# St1x.net
KiCad netlist of a schematic drawn in Altium Designer
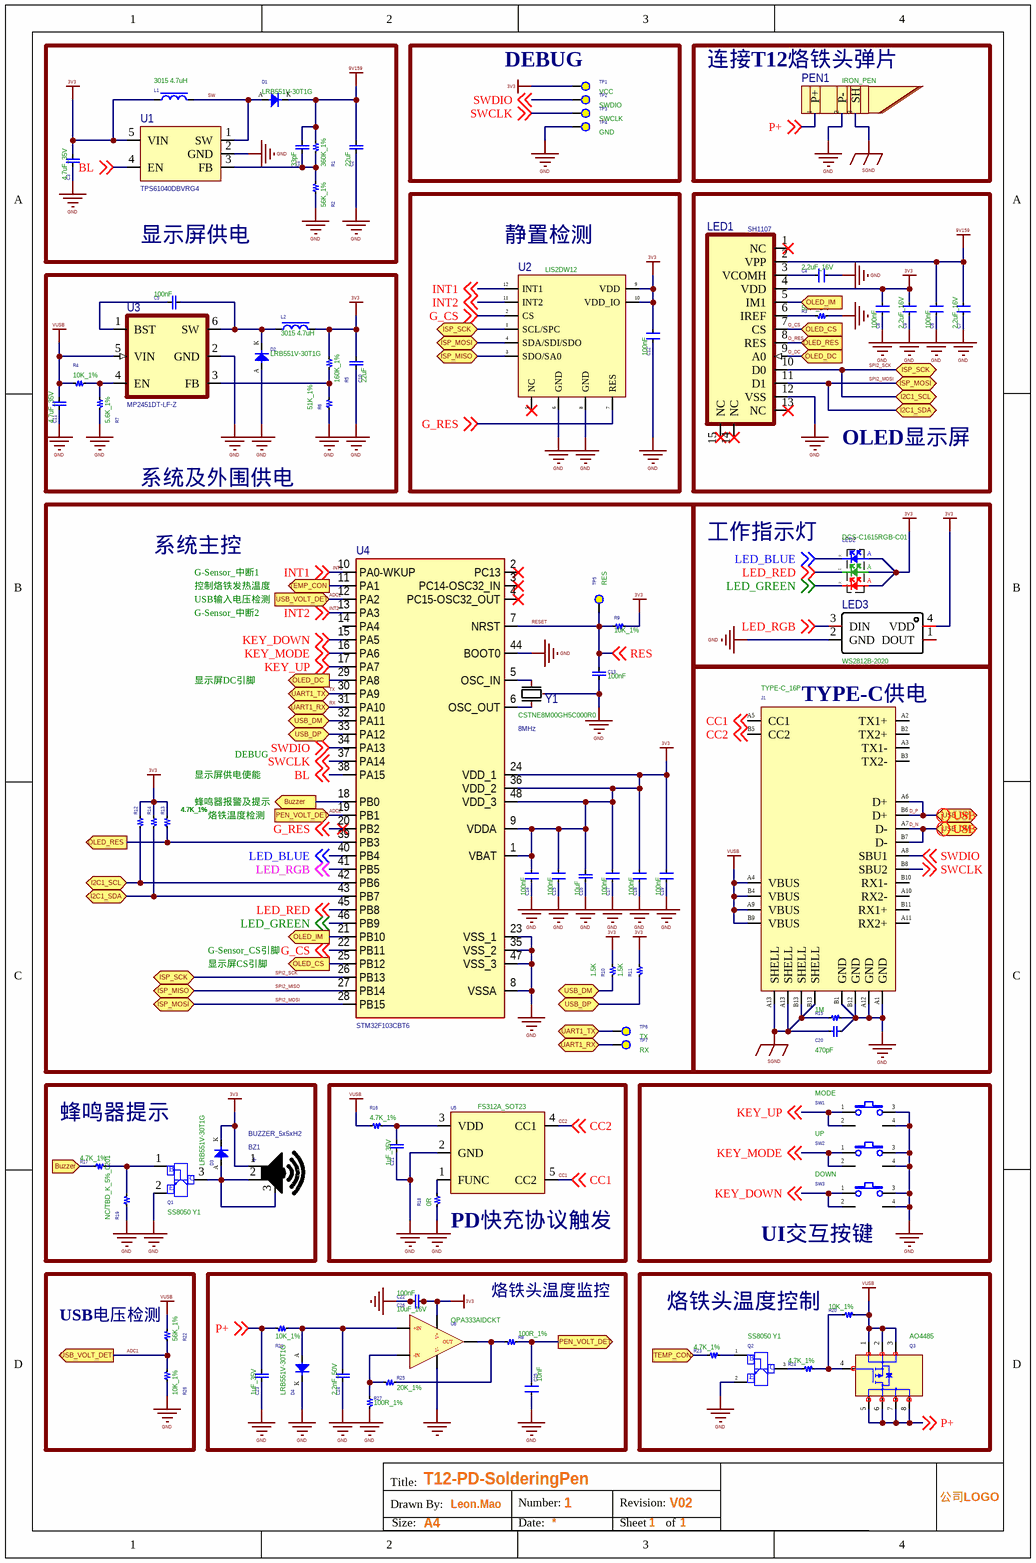
[diagram p0: St1x.SchDoc]

(export (version "E")
  (design (tool "Eeschema 10.0.6"))
  (components
    (comp (ref "BZ1")
      (value "BUZZER_5x5xH2")
      (footprint "BUZ-SMD_GSC5025YA")
      (description "电磁无源蜂鸣器(外部驱动)")
      (libsource (lib "SCHLIB_2022") (part "BZ"))
    )
    (comp (ref "C1")
      (value "33pF")
      (footprint "C1U0402")
      (description "贴片电容")
      (libsource (lib "SCHLIB_2022") (part "CAP_NP"))
    )
    (comp (ref "C2")
      (value "22uF")
      (footprint "CL0603")
      (description "贴片电容")
      (libsource (lib "SCHLIB_2022") (part "CAP_NP"))
    )
    (comp (ref "C3")
      (value "4.7uF_35V")
      (footprint "C4U0402")
      (description "贴片电容")
      (libsource (lib "SCHLIB_2022") (part "CAP_NP"))
    )
    (comp (ref "C4")
      (value "2.2uF_16V")
      (footprint "C4U0402")
      (description "贴片电容")
      (libsource (lib "") (part "CAP_NP_1"))
    )
    (comp (ref "C5")
      (value "100nF")
      (footprint "C1U0402")
      (description "贴片电容")
      (libsource (lib "SCHLIB_2022") (part "CAP_NP"))
    )
    (comp (ref "C6")
      (value "100nF")
      (footprint "C1U0402")
      (description "贴片电容")
      (libsource (lib "") (part "CAP_NP_1"))
    )
    (comp (ref "C7")
      (value "2.2uF_16V")
      (footprint "C4U0402")
      (description "贴片电容")
      (libsource (lib "") (part "CAP_NP_1"))
    )
    (comp (ref "C8")
      (value "100nF")
      (footprint "C1U0402")
      (description "贴片电容")
      (libsource (lib "") (part "CAP_NP_1"))
    )
    (comp (ref "C9")
      (value "2.2uF_16V")
      (footprint "C4U0402")
      (description "贴片电容")
      (libsource (lib "") (part "CAP_NP_1"))
    )
    (comp (ref "C10")
      (value "22uF")
      (footprint "CL0603")
      (description "贴片电容")
      (libsource (lib "SCHLIB_2022") (part "CAP_NP"))
    )
    (comp (ref "C11")
      (value "4.7uF_35V")
      (footprint "C4U0402")
      (description "贴片电容")
      (libsource (lib "SCHLIB_2022") (part "CAP_NP"))
    )
    (comp (ref "C12")
      (value "100nF")
      (footprint "C1U0402")
      (description "贴片电容")
      (libsource (lib "") (part "CAP_NP_1"))
    )
    (comp (ref "C13")
      (value "100nF")
      (footprint "C1U0402")
      (description "贴片电容")
      (libsource (lib "SCHLIB_2022") (part "CAP_NP"))
    )
    (comp (ref "C14")
      (value "100nF")
      (footprint "C1U0402")
      (description "贴片电容")
      (libsource (lib "") (part "CAP_NP_1"))
    )
    (comp (ref "C15")
      (value "100nF")
      (footprint "C1U0402")
      (description "贴片电容")
      (libsource (lib "") (part "CAP_NP_1"))
    )
    (comp (ref "C16")
      (value "10uF")
      (footprint "C4U0402")
      (description "贴片电容")
      (libsource (lib "SCHLIB_2022") (part "CAP_NP"))
    )
    (comp (ref "C17")
      (value "100nF")
      (footprint "C1U0402")
      (description "贴片电容")
      (libsource (lib "") (part "CAP_NP_1"))
    )
    (comp (ref "C18")
      (value "100nF")
      (footprint "C1U0402")
      (description "贴片电容")
      (libsource (lib "") (part "CAP_NP_1"))
    )
    (comp (ref "C19")
      (value "100nF")
      (footprint "C1U0402")
      (description "贴片电容")
      (libsource (lib "") (part "CAP_NP_1"))
    )
    (comp (ref "C20")
      (value "470pF")
      (footprint "C0402")
      (description "贴片电容")
      (libsource (lib "Leon") (part "CAP NP_1"))
    )
    (comp (ref "C21")
      (value "1uF_35V")
      (footprint "C1U0402")
      (description "贴片电容")
      (libsource (lib "SCHLIB_2022") (part "CAP_NP"))
    )
    (comp (ref "C22")
      (value "100nF")
      (footprint "C1U0402")
      (description "贴片电容")
      (libsource (lib "SCHLIB_2022") (part "CAP_NP"))
    )
    (comp (ref "C23")
      (value "1uF_35V")
      (footprint "C1U0402")
      (description "贴片电容")
      (libsource (lib "SCHLIB_2022") (part "CAP_NP"))
    )
    (comp (ref "C24")
      (value "2.2nF_50V")
      (footprint "C4U0402")
      (description "贴片电容")
      (libsource (lib "SCHLIB_2022") (part "CAP_NP"))
    )
    (comp (ref "C25")
      (value "10nF")
      (footprint "C1U0402")
      (description "贴片电容")
      (libsource (lib "") (part "CAP_NP_1"))
    )
    (comp (ref "C26")
      (value "10uF_16V")
      (footprint "C4U0402")
      (description "贴片电容")
      (libsource (lib "SCHLIB_2022") (part "CAP_NP"))
    )
    (comp (ref "D1")
      (value "LRB551V-30T1G")
      (footprint "SOD-323_AK")
      (description "肖特基二极管")
      (libsource (lib "Leon") (part "DIODE"))
    )
    (comp (ref "D2")
      (value "LRB551V-30T1G")
      (footprint "SOD-323_AK")
      (description "肖特基二极管")
      (libsource (lib "Leon") (part "DIODE"))
    )
    (comp (ref "D3")
      (value "LRB551V-30T1G")
      (footprint "SOD-323_AK")
      (description "肖特基二极管")
      (libsource (lib "Leon") (part "DIODE"))
    )
    (comp (ref "D4")
      (value "LRB551V-30T1G")
      (footprint "SOD-323_AK")
      (description "肖特基二极管")
      (libsource (lib "Leon") (part "DIODE"))
    )
    (comp (ref "J1")
      (value "TYPE-C_16P")
      (footprint "TYPE-C_16P")
      (description "TYPE-C母座")
      (libsource (lib "Leon") (part "TYPE-C_RI"))
    )
    (comp (ref "L1")
      (value "3015 4.7uH")
      (footprint "INDC3015")
      (description "功率电感")
      (libsource (lib "SCHLIB_2022") (part "INDUCTOR_2"))
    )
    (comp (ref "L2")
      (value "3015 4.7uH")
      (footprint "INDC3015")
      (description "功率电感")
      (libsource (lib "") (part "INDUCTOR_2_1"))
    )
    (comp (ref "LED1")
      (value "SH1107")
      (footprint "CON_13P_0.7mm-FPC")
      (description "QG-2880TSWKG01")
      (fields
        (field (name "MF") "{'manufacturer': u'Texas Instruments'}")
        (field (name "MP") "LP2985AIM5-5.0")
      )
      (libsource (lib "SCHLIB_2022") (part "SH1107"))
    )
    (comp (ref "LED2")
      (value "DCS-C1615RGB-C01")
      (footprint "RGB_DCS-C1615RGB-C01")
      (description "红绿蓝三色发光二极管")
      (libsource (lib "Leon") (part "LED_RGBS"))
    )
    (comp (ref "LED3")
      (value "WS2812B-2020")
      (footprint "LED_2020")
      (fields (field (name "MANUFACTURER PART") "Yo-WS2812B-3528反贴雾状"))
      (libsource (lib "altium-import") (part "root_0_mirrored_YO-WS2812B-3528反贴_"))
    )
    (comp (ref "PEN1") (value "IRON_PEN") (footprint "T13") (libsource (lib "SCHLIB_2022") (part "IRON_PEN")))
    (comp (ref "Q1")
      (value "SS8050 Y1")
      (footprint "SOT-23_123")
      (description "NPN三极管")
      (libsource (lib "PCBDEV_Library") (part "NPN"))
    )
    (comp (ref "Q2")
      (value "SS8050 Y1")
      (footprint "SOT-23_123")
      (description "NPN三极管")
      (libsource (lib "SCHLIB_2022") (part "NPN"))
    )
    (comp (ref "Q3")
      (value "AO4485")
      (footprint "SO-8M")
      (description "P沟道 40V 10A")
      (libsource (lib "SCHLIB_2022") (part "AO4485"))
    )
    (comp (ref "R1")
      (value "360K_1%")
      (footprint "RN0402")
      (description "贴片电阻")
      (libsource (lib "Leon") (part "ResSemi_3"))
    )
    (comp (ref "R2")
      (value "56K_1%")
      (footprint "RN0402")
      (description "贴片电阻")
      (libsource (lib "Leon") (part "ResSemi_3"))
    )
    (comp (ref "R3")
      (value "560k_1%")
      (footprint "RN0402")
      (description "贴片电阻")
      (libsource (lib "Leon") (part "ResSemi_3"))
    )
    (comp (ref "R4")
      (value "10K_1%")
      (footprint "RN0402")
      (description "贴片电阻")
      (libsource (lib "Leon") (part "ResSemi_3"))
    )
    (comp (ref "R5")
      (value "160K_1%")
      (footprint "RN0402")
      (description "贴片电阻")
      (libsource (lib "Leon") (part "ResSemi_3"))
    )
    (comp (ref "R6")
      (value "51K_1%")
      (footprint "RN0402")
      (description "贴片电阻")
      (libsource (lib "Leon") (part "ResSemi_3"))
    )
    (comp (ref "R7")
      (value "5.6K_1%")
      (footprint "RN0402")
      (description "贴片电阻")
      (libsource (lib "Leon") (part "ResSemi_3"))
    )
    (comp (ref "R8")
      (value "100R_1%")
      (footprint "RN0402")
      (description "贴片电阻")
      (libsource (lib "Leon") (part "ResSemi_3"))
    )
    (comp (ref "R9")
      (value "10K_1%")
      (footprint "RN0402")
      (description "贴片电阻")
      (libsource (lib "Leon") (part "ResSemi_3"))
    )
    (comp (ref "R10")
      (value "1.5K")
      (footprint "RN0402")
      (description "贴片电阻")
      (libsource (lib "Leon") (part "ResSemi_3"))
    )
    (comp (ref "R11")
      (value "1.5K")
      (footprint "RN0402")
      (description "贴片电阻")
      (libsource (lib "Leon") (part "ResSemi_3"))
    )
    (comp (ref "R12")
      (value "4.7K_1%")
      (footprint "RN0402")
      (description "贴片电阻")
      (libsource (lib "Leon") (part "ResSemi_3"))
    )
    (comp (ref "R13")
      (value "4.7K_1%")
      (footprint "RN0402")
      (description "贴片电阻")
      (libsource (lib "Leon") (part "ResSemi_3"))
    )
    (comp (ref "R14")
      (value "4.7K_1%")
      (footprint "RN0402")
      (description "贴片电阻")
      (libsource (lib "Leon") (part "ResSemi_3"))
    )
    (comp (ref "R15")
      (value "1M")
      (footprint "RN0402")
      (description "贴片电阻")
      (libsource (lib "Leon") (part "ResSemi_3"))
    )
    (comp (ref "R16")
      (value "4.7K_1%")
      (footprint "RN0402")
      (description "贴片电阻")
      (libsource (lib "Leon") (part "ResSemi_3"))
    )
    (comp (ref "R17")
      (value "4.7K_1%")
      (footprint "RN0402")
      (description "贴片电阻")
      (libsource (lib "Leon") (part "ResSemi_3"))
    )
    (comp (ref "R18")
      (value "0R")
      (footprint "RN0402")
      (description "贴片电阻")
      (libsource (lib "Leon") (part "ResSemi_3"))
    )
    (comp (ref "R19")
      (value "NC/TBD_K_5%_0201")
      (footprint "RN0402")
      (description "贴片电阻")
      (libsource (lib "Leon") (part "ResSemi_3"))
    )
    (comp (ref "R20")
      (value "10K_1%")
      (footprint "RN0402")
      (description "贴片电阻")
      (libsource (lib "Leon") (part "ResSemi_3"))
    )
    (comp (ref "R21")
      (value "10K_1%")
      (footprint "RN0603")
      (description "贴片电阻")
      (libsource (lib "Leon") (part "ResSemi_3"))
    )
    (comp (ref "R22")
      (value "56K_1%")
      (footprint "RN0402")
      (description "贴片电阻")
      (libsource (lib "Leon") (part "ResSemi_3"))
    )
    (comp (ref "R23")
      (value "4.7K_1%")
      (footprint "RN0402")
      (description "贴片电阻")
      (libsource (lib "Leon") (part "ResSemi_3"))
    )
    (comp (ref "R24")
      (value "4.7K_1%")
      (footprint "RN0402")
      (description "贴片电阻")
      (libsource (lib "Leon") (part "ResSemi_3"))
    )
    (comp (ref "R25")
      (value "20K_1%")
      (footprint "RN0402")
      (description "贴片电阻")
      (libsource (lib "Leon") (part "ResSemi_3"))
    )
    (comp (ref "R26")
      (value "10K_1%")
      (footprint "RN0402")
      (description "贴片电阻")
      (libsource (lib "Leon") (part "ResSemi_3"))
    )
    (comp (ref "R27")
      (value "100R_1%")
      (footprint "RN0402")
      (description "贴片电阻")
      (libsource (lib "Leon") (part "ResSemi_3"))
    )
    (comp (ref "SW1")
      (value "MODE")
      (footprint "KEY-SMD_4P-L4.2-W3.2-P2.20-LS5.1-TL")
      (description "轻触开关")
      (libsource (lib "SCHLIB_2022") (part "SW PUSHBUTTON"))
    )
    (comp (ref "SW2")
      (value "UP")
      (footprint "KEY-SMD_4P-L4.2-W3.2-P2.20-LS5.1-TL")
      (description "轻触开关")
      (libsource (lib "SCHLIB_2022") (part "SW PUSHBUTTON"))
    )
    (comp (ref "SW3")
      (value "DOWN")
      (footprint "KEY-SMD_4P-L4.2-W3.2-P2.20-LS5.1-TL")
      (description "轻触开关")
      (libsource (lib "SCHLIB_2022") (part "SW PUSHBUTTON"))
    )
    (comp (ref "TP1") (value "VCC") (footprint "SMD0808") (libsource (lib "SCHLIB_2022") (part "TEST")))
    (comp (ref "TP2") (value "SWDIO") (footprint "SMD0808") (libsource (lib "SCHLIB_2022") (part "TEST")))
    (comp (ref "TP3") (value "SWCLK") (footprint "SMD0808") (libsource (lib "SCHLIB_2022") (part "TEST")))
    (comp (ref "TP4") (value "GND") (footprint "SMD0808") (libsource (lib "SCHLIB_2022") (part "TEST")))
    (comp (ref "TP5") (value "RES") (footprint "SMD0808") (libsource (lib "SCHLIB_2022") (part "TEST")))
    (comp (ref "TP6") (value "TX") (footprint "SMD0808") (libsource (lib "SCHLIB_2022") (part "TEST")))
    (comp (ref "TP7") (value "RX") (footprint "SMD0808") (libsource (lib "SCHLIB_2022") (part "TEST")))
    (comp (ref "U1")
      (value "TPS61040DBVRG4")
      (footprint "SOT23-5")
      (description "DC-DC芯片")
      (libsource (lib "SCHLIB_2022") (part "TPS61040DBVRG4_[C7722]"))
    )
    (comp (ref "U2")
      (value "LIS2DW12")
      (footprint "LGA12_20x20x07")
      (libsource (lib "SCHLIB_2022") (part "LIS2DW12"))
    )
    (comp (ref "U3")
      (value "MP2451DT-LF-Z")
      (footprint "SOT23-6")
      (fields
        (field (name "MF") "{'manufacturer': u'Texas Instruments'}")
        (field (name "MP") "LP2985AIM5-5.0")
      )
      (libsource (lib "SCHLIB_2022") (part "MP2451DT-LF-Z"))
    )
    (comp (ref "U4")
      (value "STM32F103CBT6")
      (footprint "LQFP48-7x7mm")
      (description "No Description Available")
      (fields (field (name "COPYRIGHT") "Copyright (C) 2023 Ultra Librarian. All rights reserved."))
      (libsource (lib "SCHLIB_2022") (part "STM32F103CBT6"))
    )
    (comp (ref "U5")
      (value "FS312A_SOT23")
      (footprint "SOT23-5")
      (description "USB Type-C PD快充协议智能触发芯片")
      (libsource (lib "SCHLIB_2022") (part "FS312A"))
    )
    (comp (ref "U6")
      (value "OPA333AIDCKT")
      (footprint "SOT23-5")
      (libsource (lib "SCHLIB_2022") (part "OPA333_SOT23"))
    )
    (comp (ref "Y1")
      (value "CSTNE8M00GH5C000R0")
      (footprint "OSC-SMD_3P-L3.2-W1.3-P1.20-L")
      (description "频率:8MHz;频率容差:±0.07%;内藏负载电容:33pF;谐振阻抗:40Ω;")
      (fields (field (name "MANUFACTURER") "muRata(村田)") (field (name "ALTIUM_VALUE") "8MHz"))
      (libsource (lib "SCHLIB_2022") (part "CSTNE8M00GH5C000R0"))
    )
  )
  (nets
    (net (code "1") (name "/ADC1") (class "Default")
      (node (ref "R22") (pin "1") (pinfunction "1_1") (pintype "passive"))
      (node (ref "R26") (pin "2") (pinfunction "2_2") (pintype "passive"))
      (node (ref "U4") (pin "12") (pinfunction "PA2_12") (pintype "passive"))
    )
    (net (code "2") (name "/ADC2") (class "Default")
      (node (ref "C25") (pin "1") (pinfunction "1_1") (pintype "passive"))
      (node (ref "R8") (pin "1") (pinfunction "1_1") (pintype "passive"))
      (node (ref "U4") (pin "19") (pinfunction "PB1_19") (pintype "passive"))
    )
    (net (code "3") (name "/Buzzer") (class "Default")
      (node (ref "R17") (pin "1") (pinfunction "1_1") (pintype "passive"))
      (node (ref "U4") (pin "18") (pinfunction "PB0_18") (pintype "passive"))
    )
    (net (code "4") (name "/D_N") (class "Default")
      (node (ref "J1") (pin "A7") (pinfunction "D-_A7") (pintype "passive"))
      (node (ref "J1") (pin "B7") (pinfunction "D-_B7") (pintype "passive"))
      (node (ref "R10") (pin "2") (pinfunction "2_2") (pintype "passive"))
      (node (ref "U4") (pin "32") (pinfunction "PA11_32") (pintype "passive"))
    )
    (net (code "5") (name "/D_P") (class "Default")
      (node (ref "J1") (pin "A6") (pinfunction "D+_A6") (pintype "passive"))
      (node (ref "J1") (pin "B6") (pinfunction "D+_B6") (pintype "passive"))
      (node (ref "R11") (pin "2") (pinfunction "2_2") (pintype "passive"))
      (node (ref "U4") (pin "33") (pinfunction "PA12_33") (pintype "passive"))
    )
    (net (code "6") (name "/OLED_IM") (class "Default")
      (node (ref "LED1") (pin "5") (pinfunction "IM1_5") (pintype "passive"))
      (node (ref "U4") (pin "21") (pinfunction "PB10_21") (pintype "passive"))
    )
    (net (code "7") (name "/O_CS") (class "Default")
      (node (ref "LED1") (pin "7") (pinfunction "CS_7") (pintype "passive"))
      (node (ref "U4") (pin "25") (pinfunction "PB12_25") (pintype "passive"))
    )
    (net (code "8") (name "/O_DC") (class "Default")
      (node (ref "LED1") (pin "9") (pinfunction "A0_9") (pintype "input"))
      (node (ref "U4") (pin "29") (pinfunction "PA8_29") (pintype "passive"))
    )
    (net (code "9") (name "/O_RES") (class "Default")
      (node (ref "LED1") (pin "8") (pinfunction "RES_8") (pintype "passive"))
      (node (ref "R13") (pin "2") (pinfunction "2_2") (pintype "passive"))
      (node (ref "U4") (pin "39") (pinfunction "PB3_39") (pintype "passive"))
    )
    (net (code "10") (name "/RX") (class "Default")
      (node (ref "TP7") (pin "1") (pinfunction "1_1") (pintype "passive"))
      (node (ref "U4") (pin "31") (pinfunction "PA10_31") (pintype "passive"))
    )
    (net (code "11") (name "/SPI2_MISO") (class "Default")
      (node (ref "U2") (pin "3") (pinfunction "SDO/SA0_3") (pintype "passive"))
      (node (ref "U4") (pin "27") (pinfunction "PB14_27") (pintype "passive"))
    )
    (net (code "12") (name "/SPI2_MOSI") (class "Default")
      (node (ref "LED1") (pin "11") (pinfunction "D1_11") (pintype "passive"))
      (node (ref "R14") (pin "1") (pinfunction "1_1") (pintype "passive"))
      (node (ref "U2") (pin "4") (pinfunction "SDA/SDI/SDO_4") (pintype "passive"))
      (node (ref "U4") (pin "28") (pinfunction "PB15_28") (pintype "passive"))
      (node (ref "U4") (pin "43") (pinfunction "PB7_43") (pintype "passive"))
    )
    (net (code "13") (name "/SPI2_SCK") (class "Default")
      (node (ref "LED1") (pin "10") (pinfunction "D0_10") (pintype "passive"))
      (node (ref "R12") (pin "1") (pinfunction "1_1") (pintype "passive"))
      (node (ref "U2") (pin "1") (pinfunction "SCL/SPC_1") (pintype "passive"))
      (node (ref "U4") (pin "26") (pinfunction "PB13_26") (pintype "passive"))
      (node (ref "U4") (pin "42") (pinfunction "PB6_42") (pintype "passive"))
    )
    (net (code "14") (name "/SW") (class "Default")
      (node (ref "D1") (pin "A") (pinfunction "ANODE_A") (pintype "passive"))
      (node (ref "L1") (pin "2") (pinfunction "2_2") (pintype "passive"))
      (node (ref "U1") (pin "1") (pinfunction "SW_1") (pintype "passive"))
    )
    (net (code "15") (name "/TEMP_CON") (class "Default")
      (node (ref "R23") (pin "1") (pinfunction "1_1") (pintype "passive"))
      (node (ref "U4") (pin "11") (pinfunction "PA1_11") (pintype "passive"))
    )
    (net (code "16") (name "/TX") (class "Default")
      (node (ref "TP6") (pin "1") (pinfunction "1_1") (pintype "passive"))
      (node (ref "U4") (pin "30") (pinfunction "PA9_30") (pintype "passive"))
    )
    (net (code "17") (name "3V3") (class "Default")
      (node (ref "BZ1") (pin "1") (pinfunction "+_1") (pintype "passive"))
      (node (ref "C10") (pin "2") (pinfunction "2_2") (pintype "passive"))
      (node (ref "C12") (pin "1") (pinfunction "1_1") (pintype "passive"))
      (node (ref "C14") (pin "1") (pinfunction "1_1") (pintype "passive"))
      (node (ref "C15") (pin "1") (pinfunction "1_1") (pintype "passive"))
      (node (ref "C16") (pin "2") (pinfunction "2_2") (pintype "passive"))
      (node (ref "C17") (pin "1") (pinfunction "1_1") (pintype "passive"))
      (node (ref "C18") (pin "1") (pinfunction "1_1") (pintype "passive"))
      (node (ref "C19") (pin "1") (pinfunction "1_1") (pintype "passive"))
      (node (ref "C22") (pin "2") (pinfunction "2_2") (pintype "passive"))
      (node (ref "C26") (pin "1") (pinfunction "1_1") (pintype "passive"))
      (node (ref "C3") (pin "2") (pinfunction "2_2") (pintype "passive"))
      (node (ref "C8") (pin "1") (pinfunction "1_1") (pintype "passive"))
      (node (ref "C9") (pin "1") (pinfunction "1_1") (pintype "passive"))
      (node (ref "D3") (pin "K") (pinfunction "CATHODE_K") (pintype "passive"))
      (node (ref "L1") (pin "1") (pinfunction "1_1") (pintype "passive"))
      (node (ref "L2") (pin "1") (pinfunction "1_1") (pintype "passive"))
      (node (ref "LED1") (pin "4") (pinfunction "VDD_4") (pintype "power_in"))
      (node (ref "LED2") (pin "A") (pinfunction "A_A") (pintype "passive"))
      (node (ref "LED3") (pin "4") (pinfunction "VDD_4") (pintype "passive"))
      (node (ref "R10") (pin "1") (pinfunction "1_1") (pintype "passive"))
      (node (ref "R11") (pin "1") (pinfunction "1_1") (pintype "passive"))
      (node (ref "R12") (pin "2") (pinfunction "2_2") (pintype "passive"))
      (node (ref "R13") (pin "1") (pinfunction "1_1") (pintype "passive"))
      (node (ref "R14") (pin "2") (pinfunction "2_2") (pintype "passive"))
      (node (ref "R5") (pin "1") (pinfunction "1_1") (pintype "passive"))
      (node (ref "R9") (pin "1") (pinfunction "1_1") (pintype "passive"))
      (node (ref "TP1") (pin "1") (pinfunction "1_1") (pintype "passive"))
      (node (ref "U1") (pin "5") (pinfunction "VIN_5") (pintype "passive"))
      (node (ref "U2") (pin "10") (pinfunction "VDD_IO_10") (pintype "passive"))
      (node (ref "U2") (pin "9") (pinfunction "VDD_9") (pintype "passive"))
      (node (ref "U4") (pin "1") (pinfunction "VBAT_1") (pintype "power_in"))
      (node (ref "U4") (pin "24") (pinfunction "VDD_1_24") (pintype "power_in"))
      (node (ref "U4") (pin "36") (pinfunction "VDD_2_36") (pintype "power_in"))
      (node (ref "U4") (pin "48") (pinfunction "VDD_3_48") (pintype "power_in"))
      (node (ref "U4") (pin "9") (pinfunction "VDDA_9") (pintype "power_in"))
      (node (ref "U6") (pin "5") (pinfunction "V+_5") (pintype "passive"))
    )
    (net (code "18") (name "9V159") (class "Default")
      (node (ref "C1") (pin "2") (pinfunction "2_2") (pintype "passive"))
      (node (ref "C2") (pin "2") (pinfunction "2_2") (pintype "passive"))
      (node (ref "C6") (pin "1") (pinfunction "1_1") (pintype "passive"))
      (node (ref "C7") (pin "1") (pinfunction "1_1") (pintype "passive"))
      (node (ref "D1") (pin "K") (pinfunction "CATHODE_K") (pintype "passive"))
      (node (ref "LED1") (pin "2") (pinfunction "VPP_2") (pintype "power_in"))
      (node (ref "R1") (pin "1") (pinfunction "1_1") (pintype "passive"))
    )
    (net (code "19") (name "BL") (class "Default")
      (node (ref "U1") (pin "4") (pinfunction "EN_4") (pintype "passive"))
      (node (ref "U4") (pin "38") (pinfunction "PA15_38") (pintype "passive"))
    )
    (net (code "20") (name "CC1") (class "Default")
      (node (ref "J1") (pin "A5") (pinfunction "CC1_A5") (pintype "passive"))
      (node (ref "U5") (pin "5") (pinfunction "CC2_5") (pintype "passive"))
    )
    (net (code "21") (name "CC2") (class "Default")
      (node (ref "J1") (pin "B5") (pinfunction "CC2_B5") (pintype "passive"))
      (node (ref "U5") (pin "4") (pinfunction "CC1_4") (pintype "passive"))
    )
    (net (code "22") (name "GND") (class "Default")
      (node (ref "C10") (pin "1") (pinfunction "1_1") (pintype "passive"))
      (node (ref "C11") (pin "1") (pinfunction "1_1") (pintype "passive"))
      (node (ref "C12") (pin "2") (pinfunction "2_2") (pintype "passive"))
      (node (ref "C13") (pin "2") (pinfunction "2_2") (pintype "passive"))
      (node (ref "C14") (pin "2") (pinfunction "2_2") (pintype "passive"))
      (node (ref "C15") (pin "2") (pinfunction "2_2") (pintype "passive"))
      (node (ref "C16") (pin "1") (pinfunction "1_1") (pintype "passive"))
      (node (ref "C17") (pin "2") (pinfunction "2_2") (pintype "passive"))
      (node (ref "C18") (pin "2") (pinfunction "2_2") (pintype "passive"))
      (node (ref "C19") (pin "2") (pinfunction "2_2") (pintype "passive"))
      (node (ref "C2") (pin "1") (pinfunction "1_1") (pintype "passive"))
      (node (ref "C20") (pin "1") (pinfunction "1_1") (pintype "passive"))
      (node (ref "C21") (pin "1") (pinfunction "1_1") (pintype "passive"))
      (node (ref "C22") (pin "1") (pinfunction "1_1") (pintype "passive"))
      (node (ref "C23") (pin "2") (pinfunction "2_2") (pintype "passive"))
      (node (ref "C24") (pin "2") (pinfunction "2_2") (pintype "passive"))
      (node (ref "C25") (pin "2") (pinfunction "2_2") (pintype "passive"))
      (node (ref "C26") (pin "2") (pinfunction "2_2") (pintype "passive"))
      (node (ref "C3") (pin "1") (pinfunction "1_1") (pintype "passive"))
      (node (ref "C4") (pin "2") (pinfunction "2_2") (pintype "passive"))
      (node (ref "C6") (pin "2") (pinfunction "2_2") (pintype "passive"))
      (node (ref "C7") (pin "2") (pinfunction "2_2") (pintype "passive"))
      (node (ref "C8") (pin "2") (pinfunction "2_2") (pintype "passive"))
      (node (ref "C9") (pin "2") (pinfunction "2_2") (pintype "passive"))
      (node (ref "D2") (pin "A") (pinfunction "ANODE_A") (pintype "passive"))
      (node (ref "D4") (pin "K") (pinfunction "CATHODE_K") (pintype "passive"))
      (node (ref "J1") (pin "A1") (pinfunction "GND_A1") (pintype "passive"))
      (node (ref "J1") (pin "A12") (pinfunction "GND_A12") (pintype "passive"))
      (node (ref "J1") (pin "B1") (pinfunction "GND_B1") (pintype "passive"))
      (node (ref "J1") (pin "B12") (pinfunction "GND_B12") (pintype "passive"))
      (node (ref "LED1") (pin "12") (pinfunction "VSS_12") (pintype "passive"))
      (node (ref "LED3") (pin "2") (pinfunction "GND_2") (pintype "passive"))
      (node (ref "PEN1") (pin "2") (pinfunction "P-_2") (pintype "passive"))
      (node (ref "Q1") (pin "2") (pinfunction "EMITTER_2") (pintype "passive"))
      (node (ref "Q2") (pin "2") (pinfunction "EMITTER_2") (pintype "passive"))
      (node (ref "R15") (pin "2") (pinfunction "2_2") (pintype "passive"))
      (node (ref "R18") (pin "2") (pinfunction "2_2") (pintype "passive"))
      (node (ref "R19") (pin "1") (pinfunction "1_1") (pintype "passive"))
      (node (ref "R2") (pin "1") (pinfunction "1_1") (pintype "passive"))
      (node (ref "R26") (pin "1") (pinfunction "1_1") (pintype "passive"))
      (node (ref "R27") (pin "2") (pinfunction "2_2") (pintype "passive"))
      (node (ref "R3") (pin "1") (pinfunction "1_1") (pintype "passive"))
      (node (ref "R6") (pin "1") (pinfunction "1_1") (pintype "passive"))
      (node (ref "R7") (pin "2") (pinfunction "2_2") (pintype "passive"))
      (node (ref "SW1") (pin "3") (pinfunction "3_3") (pintype "passive"))
      (node (ref "SW1") (pin "4") (pinfunction "4_4") (pintype "passive"))
      (node (ref "SW2") (pin "3") (pinfunction "3_3") (pintype "passive"))
      (node (ref "SW2") (pin "4") (pinfunction "4_4") (pintype "passive"))
      (node (ref "SW3") (pin "3") (pinfunction "3_3") (pintype "passive"))
      (node (ref "SW3") (pin "4") (pinfunction "4_4") (pintype "passive"))
      (node (ref "TP4") (pin "1") (pinfunction "1_1") (pintype "passive"))
      (node (ref "U1") (pin "2") (pinfunction "GND_2") (pintype "passive"))
      (node (ref "U2") (pin "6") (pinfunction "GND_6") (pintype "passive"))
      (node (ref "U2") (pin "8") (pinfunction "GND_8") (pintype "passive"))
      (node (ref "U3") (pin "2") (pinfunction "GND_2") (pintype "power_in"))
      (node (ref "U4") (pin "23") (pinfunction "VSS_1_23") (pintype "power_in"))
      (node (ref "U4") (pin "35") (pinfunction "VSS_2_35") (pintype "power_in"))
      (node (ref "U4") (pin "44") (pinfunction "BOOT0_44") (pintype "passive"))
      (node (ref "U4") (pin "47") (pinfunction "VSS_3_47") (pintype "power_in"))
      (node (ref "U4") (pin "8") (pinfunction "VSSA_8") (pintype "power_in"))
      (node (ref "U5") (pin "2") (pinfunction "GND_2") (pintype "passive"))
      (node (ref "U6") (pin "2") (pinfunction "V-_2") (pintype "passive"))
      (node (ref "Y1") (pin "2") (pinfunction "GND_2") (pintype "passive"))
    )
    (net (code "23") (name "G_CS") (class "Default")
      (node (ref "U2") (pin "2") (pinfunction "CS_2") (pintype "passive"))
      (node (ref "U4") (pin "22") (pinfunction "PB11_22") (pintype "passive"))
    )
    (net (code "24") (name "G_RES") (class "Default")
      (node (ref "U2") (pin "7") (pinfunction "RES_7") (pintype "passive"))
      (node (ref "U4") (pin "20") (pinfunction "PB2_20") (pintype "passive"))
    )
    (net (code "25") (name "INT1") (class "Default")
      (node (ref "U2") (pin "12") (pinfunction "INT1_12") (pintype "passive"))
      (node (ref "U4") (pin "10") (pinfunction "PA0-WKUP_10") (pintype "passive"))
    )
    (net (code "26") (name "INT2") (class "Default")
      (node (ref "U2") (pin "11") (pinfunction "INT2_11") (pintype "passive"))
      (node (ref "U4") (pin "13") (pinfunction "PA3_13") (pintype "passive"))
    )
    (net (code "27") (name "KEY_DOWN") (class "Default")
      (node (ref "SW3") (pin "1") (pinfunction "1_1") (pintype "passive"))
      (node (ref "SW3") (pin "2") (pinfunction "2_2") (pintype "passive"))
      (node (ref "U4") (pin "15") (pinfunction "PA5_15") (pintype "passive"))
    )
    (net (code "28") (name "KEY_MODE") (class "Default")
      (node (ref "SW2") (pin "1") (pinfunction "1_1") (pintype "passive"))
      (node (ref "SW2") (pin "2") (pinfunction "2_2") (pintype "passive"))
      (node (ref "U4") (pin "16") (pinfunction "PA6_16") (pintype "passive"))
    )
    (net (code "29") (name "KEY_UP") (class "Default")
      (node (ref "SW1") (pin "1") (pinfunction "1_1") (pintype "passive"))
      (node (ref "SW1") (pin "2") (pinfunction "2_2") (pintype "passive"))
      (node (ref "U4") (pin "17") (pinfunction "PA7_17") (pintype "passive"))
    )
    (net (code "30") (name "LED_BLUE") (class "Default")
      (node (ref "LED2") (pin "BC") (pinfunction "BC_BC") (pintype "passive"))
      (node (ref "U4") (pin "40") (pinfunction "PB4_40") (pintype "passive"))
    )
    (net (code "31") (name "LED_GREEN") (class "Default")
      (node (ref "LED2") (pin "RC") (pinfunction "RC_RC") (pintype "passive"))
      (node (ref "U4") (pin "46") (pinfunction "PB9_46") (pintype "passive"))
    )
    (net (code "32") (name "LED_RED") (class "Default")
      (node (ref "LED2") (pin "GC") (pinfunction "GC_GC") (pintype "passive"))
      (node (ref "U4") (pin "45") (pinfunction "PB8_45") (pintype "passive"))
    )
    (net (code "33") (name "LED_RGB") (class "Default")
      (node (ref "LED3") (pin "3") (pinfunction "DIN_3") (pintype "passive"))
      (node (ref "U4") (pin "41") (pinfunction "PB5_41") (pintype "passive"))
    )
    (net (code "34") (name "Net-(D2-CATHODE)") (class "Default")
      (node (ref "C5") (pin "1") (pinfunction "1_1") (pintype "passive"))
      (node (ref "D2") (pin "K") (pinfunction "CATHODE_K") (pintype "passive"))
      (node (ref "L2") (pin "2") (pinfunction "2_2") (pintype "passive"))
      (node (ref "U3") (pin "6") (pinfunction "SW_6") (pintype "passive"))
    )
    (net (code "35") (name "Net-(D3-ANODE)") (class "Default")
      (node (ref "BZ1") (pin "2") (pinfunction "-_2") (pintype "passive"))
      (node (ref "BZ1") (pin "3") (pinfunction "-_3") (pintype "passive"))
      (node (ref "D3") (pin "A") (pinfunction "ANODE_A") (pintype "passive"))
      (node (ref "Q1") (pin "3") (pinfunction "COLLECTOR_3") (pintype "passive"))
    )
    (net (code "36") (name "Net-(D4-ANODE)") (class "Default")
      (node (ref "C24") (pin "1") (pinfunction "1_1") (pintype "passive"))
      (node (ref "D4") (pin "A") (pinfunction "ANODE_A") (pintype "passive"))
      (node (ref "R21") (pin "1") (pinfunction "1_1") (pintype "passive"))
      (node (ref "U6") (pin "3") (pinfunction "+IN_3") (pintype "passive"))
    )
    (net (code "37") (name "Net-(LED1-IREF)") (class "Default")
      (node (ref "LED1") (pin "6") (pinfunction "IREF_6") (pintype "passive"))
      (node (ref "R3") (pin "2") (pinfunction "2_2") (pintype "passive"))
    )
    (net (code "38") (name "Net-(LED1-VCOMH)") (class "Default")
      (node (ref "C4") (pin "1") (pinfunction "1_1") (pintype "passive"))
      (node (ref "LED1") (pin "3") (pinfunction "VCOMH_3") (pintype "passive"))
    )
    (net (code "39") (name "Net-(Q1-BASE)") (class "Default")
      (node (ref "Q1") (pin "1") (pinfunction "BASE_1") (pintype "passive"))
      (node (ref "R17") (pin "2") (pinfunction "2_2") (pintype "passive"))
      (node (ref "R19") (pin "2") (pinfunction "2_2") (pintype "passive"))
    )
    (net (code "40") (name "Net-(Q2-BASE)") (class "Default")
      (node (ref "Q2") (pin "1") (pinfunction "BASE_1") (pintype "passive"))
      (node (ref "R23") (pin "2") (pinfunction "2_2") (pintype "passive"))
    )
    (net (code "41") (name "Net-(Q2-COLLECTOR)") (class "Default")
      (node (ref "Q2") (pin "3") (pinfunction "COLLECTOR_3") (pintype "passive"))
      (node (ref "R24") (pin "1") (pinfunction "1_1") (pintype "passive"))
    )
    (net (code "42") (name "Net-(Q3-G)") (class "Default")
      (node (ref "Q3") (pin "4") (pinfunction "G_4") (pintype "passive"))
      (node (ref "R20") (pin "1") (pinfunction "1_1") (pintype "passive"))
      (node (ref "R24") (pin "2") (pinfunction "2_2") (pintype "passive"))
    )
    (net (code "43") (name "Net-(U1-FB)") (class "Default")
      (node (ref "C1") (pin "1") (pinfunction "1_1") (pintype "passive"))
      (node (ref "R1") (pin "2") (pinfunction "2_2") (pintype "passive"))
      (node (ref "R2") (pin "2") (pinfunction "2_2") (pintype "passive"))
      (node (ref "U1") (pin "3") (pinfunction "FB_3") (pintype "passive"))
    )
    (net (code "44") (name "Net-(U3-BST)") (class "Default")
      (node (ref "C5") (pin "2") (pinfunction "2_2") (pintype "passive"))
      (node (ref "U3") (pin "1") (pinfunction "BST_1") (pintype "passive"))
    )
    (net (code "45") (name "Net-(U3-EN)") (class "Default")
      (node (ref "R4") (pin "1") (pinfunction "1_1") (pintype "passive"))
      (node (ref "R7") (pin "1") (pinfunction "1_1") (pintype "passive"))
      (node (ref "U3") (pin "4") (pinfunction "EN_4") (pintype "passive"))
    )
    (net (code "46") (name "Net-(U3-FB)") (class "Default")
      (node (ref "R5") (pin "2") (pinfunction "2_2") (pintype "passive"))
      (node (ref "R6") (pin "2") (pinfunction "2_2") (pintype "passive"))
      (node (ref "U3") (pin "3") (pinfunction "FB_3") (pintype "passive"))
    )
    (net (code "47") (name "Net-(U4-OSC_IN)") (class "Default")
      (node (ref "U4") (pin "5") (pinfunction "OSC_IN_5") (pintype "passive"))
      (node (ref "Y1") (pin "1") (pinfunction "OSC1_1") (pintype "passive"))
    )
    (net (code "48") (name "Net-(U4-OSC_OUT)") (class "Default")
      (node (ref "U4") (pin "6") (pinfunction "OSC_OUT_6") (pintype "passive"))
      (node (ref "Y1") (pin "3") (pinfunction "OSC2_3") (pintype "passive"))
    )
    (net (code "49") (name "Net-(U5-FUNC)") (class "Default")
      (node (ref "R18") (pin "1") (pinfunction "1_1") (pintype "passive"))
      (node (ref "U5") (pin "1") (pinfunction "FUNC_1") (pintype "passive"))
    )
    (net (code "50") (name "Net-(U5-VDD)") (class "Default")
      (node (ref "C21") (pin "2") (pinfunction "2_2") (pintype "passive"))
      (node (ref "R16") (pin "2") (pinfunction "2_2") (pintype "passive"))
      (node (ref "U5") (pin "3") (pinfunction "VDD_3") (pintype "passive"))
    )
    (net (code "51") (name "Net-(U6--IN)") (class "Default")
      (node (ref "R25") (pin "2") (pinfunction "2_2") (pintype "passive"))
      (node (ref "R27") (pin "1") (pinfunction "1_1") (pintype "passive"))
      (node (ref "U6") (pin "4") (pinfunction "-IN_4") (pintype "passive"))
    )
    (net (code "52") (name "Net-(U6-OUT)") (class "Default")
      (node (ref "R25") (pin "1") (pinfunction "1_1") (pintype "passive"))
      (node (ref "R8") (pin "2") (pinfunction "2_2") (pintype "passive"))
      (node (ref "U6") (pin "1") (pinfunction "OUT_1") (pintype "passive"))
    )
    (net (code "53") (name "P+") (class "Default")
      (node (ref "C23") (pin "1") (pinfunction "1_1") (pintype "passive"))
      (node (ref "PEN1") (pin "1") (pinfunction "P+_1") (pintype "passive"))
      (node (ref "Q3") (pin "5") (pinfunction "D_5") (pintype "passive"))
      (node (ref "Q3") (pin "6") (pinfunction "D_6") (pintype "passive"))
      (node (ref "Q3") (pin "7") (pinfunction "D_7") (pintype "passive"))
      (node (ref "Q3") (pin "8") (pinfunction "D_8") (pintype "passive"))
      (node (ref "R21") (pin "2") (pinfunction "2_2") (pintype "passive"))
    )
    (net (code "54") (name "RES") (class "Default")
      (node (ref "C13") (pin "1") (pinfunction "1_1") (pintype "passive"))
      (node (ref "R9") (pin "2") (pinfunction "2_2") (pintype "passive"))
      (node (ref "TP5") (pin "1") (pinfunction "1_1") (pintype "passive"))
      (node (ref "U4") (pin "7") (pinfunction "NRST_7") (pintype "passive"))
    )
    (net (code "55") (name "SGND") (class "Default")
      (node (ref "C20") (pin "2") (pinfunction "2_2") (pintype "passive"))
      (node (ref "J1") (pin "A13") (pinfunction "SHELL_A13") (pintype "passive"))
      (node (ref "J1") (pin "B13") (pinfunction "SHELL_B13") (pintype "passive"))
      (node (ref "PEN1") (pin "3") (pinfunction "SH_3") (pintype "passive"))
      (node (ref "R15") (pin "1") (pinfunction "1_1") (pintype "passive"))
    )
    (net (code "56") (name "SWCLK") (class "Default")
      (node (ref "J1") (pin "B8") (pinfunction "SBU2_B8") (pintype "passive"))
      (node (ref "TP3") (pin "1") (pinfunction "1_1") (pintype "passive"))
      (node (ref "U4") (pin "37") (pinfunction "PA14_37") (pintype "passive"))
    )
    (net (code "57") (name "SWDIO") (class "Default")
      (node (ref "J1") (pin "A8") (pinfunction "SBU1_A8") (pintype "passive"))
      (node (ref "TP2") (pin "1") (pinfunction "1_1") (pintype "passive"))
      (node (ref "U4") (pin "34") (pinfunction "PA13_34") (pintype "passive"))
    )
    (net (code "58") (name "VUSB") (class "Default")
      (node (ref "C11") (pin "2") (pinfunction "2_2") (pintype "passive"))
      (node (ref "J1") (pin "A4") (pinfunction "VBUS_A4") (pintype "passive"))
      (node (ref "J1") (pin "A9") (pinfunction "VBUS_A9") (pintype "passive"))
      (node (ref "J1") (pin "B4") (pinfunction "VBUS_B4") (pintype "passive"))
      (node (ref "J1") (pin "B9") (pinfunction "VBUS_B9") (pintype "passive"))
      (node (ref "Q3") (pin "1") (pinfunction "S_1") (pintype "passive"))
      (node (ref "Q3") (pin "2") (pinfunction "S_2") (pintype "passive"))
      (node (ref "Q3") (pin "3") (pinfunction "S_3") (pintype "passive"))
      (node (ref "R16") (pin "1") (pinfunction "1_1") (pintype "passive"))
      (node (ref "R20") (pin "2") (pinfunction "2_2") (pintype "passive"))
      (node (ref "R22") (pin "2") (pinfunction "2_2") (pintype "passive"))
      (node (ref "R4") (pin "2") (pinfunction "2_2") (pintype "passive"))
      (node (ref "U3") (pin "5") (pinfunction "VIN_5") (pintype "input"))
    )
    (net (code "59") (name "unconnected-(J1-RX1+-PadB11)") (class "Default")
      (node (ref "J1") (pin "B11") (pinfunction "RX1+_B11") (pintype "passive"))
    )
    (net (code "60") (name "unconnected-(J1-RX1--PadB10)") (class "Default")
      (node (ref "J1") (pin "B10") (pinfunction "RX1-_B10") (pintype "passive"))
    )
    (net (code "61") (name "unconnected-(J1-RX2+-PadA11)") (class "Default")
      (node (ref "J1") (pin "A11") (pinfunction "RX2+_A11") (pintype "passive"))
    )
    (net (code "62") (name "unconnected-(J1-RX2--PadA10)") (class "Default")
      (node (ref "J1") (pin "A10") (pinfunction "RX2-_A10") (pintype "passive"))
    )
    (net (code "63") (name "unconnected-(J1-TX1+-PadA2)") (class "Default")
      (node (ref "J1") (pin "A2") (pinfunction "TX1+_A2") (pintype "passive"))
    )
    (net (code "64") (name "unconnected-(J1-TX1--PadA3)") (class "Default")
      (node (ref "J1") (pin "A3") (pinfunction "TX1-_A3") (pintype "passive"))
    )
    (net (code "65") (name "unconnected-(J1-TX2+-PadB2)") (class "Default")
      (node (ref "J1") (pin "B2") (pinfunction "TX2+_B2") (pintype "passive"))
    )
    (net (code "66") (name "unconnected-(J1-TX2--PadB3)") (class "Default")
      (node (ref "J1") (pin "B3") (pinfunction "TX2-_B3") (pintype "passive"))
    )
    (net (code "67") (name "unconnected-(LED1-NC-Pad1)") (class "Default")
      (node (ref "LED1") (pin "1") (pinfunction "NC_1") (pintype "passive+no_connect"))
    )
    (net (code "68") (name "unconnected-(LED1-NC-Pad13)") (class "Default")
      (node (ref "LED1") (pin "13") (pinfunction "NC_13") (pintype "passive+no_connect"))
    )
    (net (code "69") (name "unconnected-(LED1-NC-Pad14)") (class "Default")
      (node (ref "LED1") (pin "14") (pinfunction "NC_14") (pintype "passive+no_connect"))
    )
    (net (code "70") (name "unconnected-(LED1-NC-Pad15)") (class "Default")
      (node (ref "LED1") (pin "15") (pinfunction "NC_15") (pintype "passive+no_connect"))
    )
    (net (code "71") (name "unconnected-(LED3-DOUT-Pad1)") (class "Default")
      (node (ref "LED3") (pin "1") (pinfunction "DOUT_1") (pintype "passive"))
    )
    (net (code "72") (name "unconnected-(U2-NC-Pad5)") (class "Default")
      (node (ref "U2") (pin "5") (pinfunction "NC_5") (pintype "passive+no_connect"))
    )
    (net (code "73") (name "unconnected-(U4-PA4-Pad14)") (class "Default")
      (node (ref "U4") (pin "14") (pinfunction "PA4_14") (pintype "passive"))
    )
    (net (code "74") (name "unconnected-(U4-PC13-Pad2)") (class "Default")
      (node (ref "U4") (pin "2") (pinfunction "PC13_2") (pintype "passive+no_connect"))
    )
    (net (code "75") (name "unconnected-(U4-PC14-OSC32_IN-Pad3)") (class "Default")
      (node (ref "U4") (pin "3") (pinfunction "PC14-OSC32_IN_3") (pintype "passive+no_connect"))
    )
    (net (code "76") (name "unconnected-(U4-PC15-OSC32_OUT-Pad4)") (class "Default")
      (node (ref "U4") (pin "4") (pinfunction "PC15-OSC32_OUT_4") (pintype "passive+no_connect"))
    )
  )
)
